# PushButton.net
KiCad netlist of a schematic drawn in Altium Designer
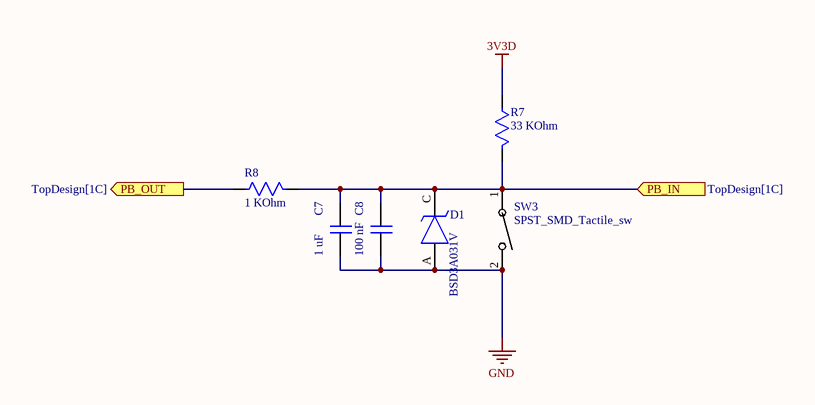
[diagram p0: PushButton.SchDoc]

(export (version "E")
  (design (tool "Eeschema 10.0.6"))
  (components
    (comp (ref "C7")
      (value "1 uF")
      (footprint "CAP_0603")
      (description "Cap SMD.")
      (libsource (lib "Aptinex_discrete") (part "Cap SMD"))
    )
    (comp (ref "C8")
      (value "100 nF")
      (footprint "CAP_0603")
      (description "Cap SMD.")
      (libsource (lib "Aptinex_discrete") (part "Cap SMD"))
    )
    (comp (ref "D1")
      (value "BSD3A031V")
      (footprint "MCC_SOD-323_IPC_A")
      (description "TVS Diode (Uni-directional)")
      (fields
        (field (name "MANUFACTURER_PART_NUMBER") "SMAJ14A")
        (field (name "MOUSER PART NUMBER") "576-SMAJ14A")
      )
      (libsource (lib "Aptinex_discrete") (part "TVS_Diode_Single"))
    )
    (comp (ref "R7")
      (value "33 KOhm")
      (footprint "Res_0603")
      (description "SMD Resistor")
      (fields (field (name "MP") "RC0805FR-07330RL") (field (name "MF") "Yageo"))
      (libsource (lib "Aptinex_discrete") (part "Res smd"))
    )
    (comp (ref "R8")
      (value "1 KOhm")
      (footprint "Res_0603")
      (description "SMD Resistor")
      (fields (field (name "MP") "RC0805FR-07330RL") (field (name "MF") "Yageo"))
      (libsource (lib "Aptinex_discrete") (part "Res smd"))
    )
    (comp (ref "SW3")
      (value "SPST_SMD_Tactile_sw")
      (footprint "SPST_SMD_6mm")
      (description "SPST SMD Tactile Switches Rectangle button Brick nogging")
      (libsource (lib "Aptinex_discrete") (part "SPST_SMD_Tactile_sw"))
    )
  )
  (nets
    (net (code "1") (name "/PB_IN") (class "Default")
      (node (ref "C7") (pin "2") (pinfunction "2_2") (pintype "passive"))
      (node (ref "C8") (pin "2") (pinfunction "2_2") (pintype "passive"))
      (node (ref "D1") (pin "C") (pinfunction "C_C") (pintype "passive"))
      (node (ref "R7") (pin "1") (pinfunction "1_1") (pintype "passive"))
      (node (ref "R8") (pin "1") (pinfunction "1_1") (pintype "passive"))
      (node (ref "SW3") (pin "1") (pinfunction "1_1") (pintype "passive"))
    )
    (net (code "2") (name "/PB_OUT") (class "Default")
      (node (ref "R8") (pin "2") (pinfunction "2_2") (pintype "passive"))
    )
    (net (code "3") (name "3V3D") (class "Default")
      (node (ref "R7") (pin "2") (pinfunction "2_2") (pintype "passive"))
    )
    (net (code "4") (name "GND") (class "Default")
      (node (ref "C7") (pin "1") (pinfunction "1_1") (pintype "passive"))
      (node (ref "C8") (pin "1") (pinfunction "1_1") (pintype "passive"))
      (node (ref "D1") (pin "A") (pinfunction "A_A") (pintype "passive"))
      (node (ref "SW3") (pin "2") (pinfunction "2_2") (pintype "passive"))
    )
  )
)
